# wire_detector.net
KiCad netlist of a schematic drawn in EAGLE
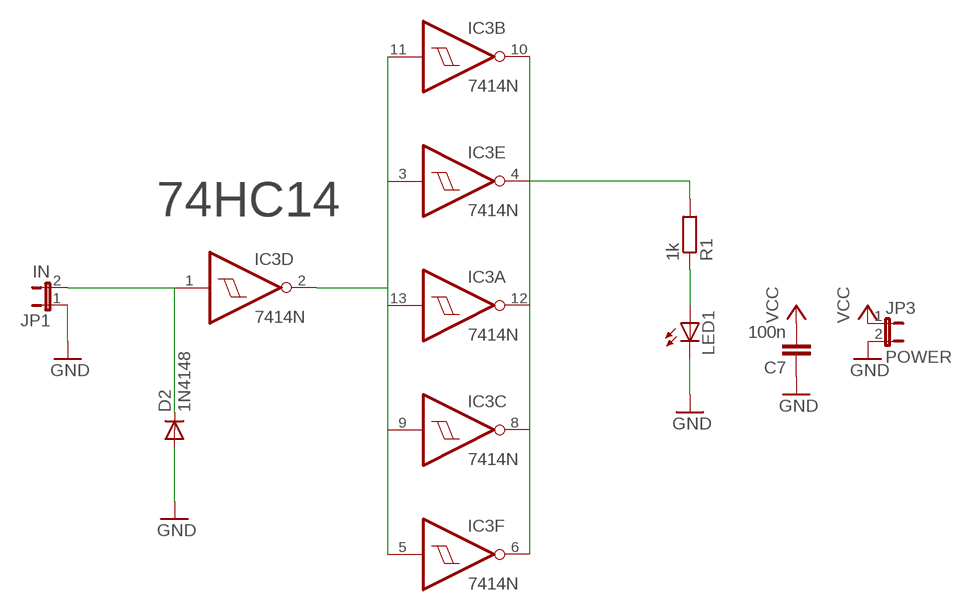
[diagram p0: schematic, sheet 1]

(export (version "E")
  (design (tool "Eeschema 10.0.6"))
  (components
    (comp (ref "C7")
      (value "100n")
      (footprint "eagle-import:C025-024X044")
      (libsource (lib "eagle-import") (part "C-EU025-024X044"))
    )
    (comp (ref "D2")
      (value "1N4148")
      (footprint "eagle-import:D-2.5")
      (libsource (lib "eagle-import") (part "DIODE-D-2.5"))
    )
    (comp (ref "IC3")
      (value "7414N")
      (footprint "eagle-import:DIL14")
      (libsource (lib "eagle-import") (part "7414N"))
    )
    (comp (ref "JP1")
      (value "IN")
      (footprint "eagle-import:JP1")
      (libsource (lib "eagle-import") (part "JP1E"))
    )
    (comp (ref "JP3")
      (value "POWER")
      (footprint "eagle-import:JP1")
      (libsource (lib "eagle-import") (part "JP1E"))
    )
    (comp (ref "LED1")
      (value "LED5MM")
      (footprint "eagle-import:LED5MM")
      (libsource (lib "eagle-import") (part "LED5MM"))
    )
    (comp (ref "R1")
      (value "1k")
      (footprint "eagle-import:0204_5")
      (libsource (lib "eagle-import") (part "R-EU_0204/5"))
    )
  )
  (nets
    (net (code "1") (name "GND") (class "Default")
      (node (ref "C7") (pin "1") (pinfunction "1_1") (pintype "passive"))
      (node (ref "D2") (pin "A") (pinfunction "A_A") (pintype "passive"))
      (node (ref "JP1") (pin "1") (pinfunction "1_1") (pintype "passive"))
      (node (ref "JP3") (pin "2") (pinfunction "2_2") (pintype "passive"))
      (node (ref "LED1") (pin "K") (pinfunction "C_K") (pintype "passive"))
    )
    (net (code "2") (name "Net-(IC3A-I)") (class "Default")
      (node (ref "IC3") (pin "11") (pinfunction "I_11") (pintype "input"))
      (node (ref "IC3") (pin "13") (pinfunction "I_13") (pintype "input"))
      (node (ref "IC3") (pin "2") (pinfunction "O_2") (pintype "output"))
      (node (ref "IC3") (pin "3") (pinfunction "I_3") (pintype "input"))
      (node (ref "IC3") (pin "5") (pinfunction "I_5") (pintype "input"))
      (node (ref "IC3") (pin "9") (pinfunction "I_9") (pintype "input"))
    )
    (net (code "3") (name "Net-(IC3A-O)") (class "Default")
      (node (ref "IC3") (pin "10") (pinfunction "O_10") (pintype "output"))
      (node (ref "IC3") (pin "12") (pinfunction "O_12") (pintype "output"))
      (node (ref "IC3") (pin "4") (pinfunction "O_4") (pintype "output"))
      (node (ref "IC3") (pin "6") (pinfunction "O_6") (pintype "output"))
      (node (ref "IC3") (pin "8") (pinfunction "O_8") (pintype "output"))
      (node (ref "R1") (pin "2") (pinfunction "2_2") (pintype "passive"))
    )
    (net (code "4") (name "Net-(IC3D-I)") (class "Default")
      (node (ref "D2") (pin "C") (pinfunction "C_C") (pintype "passive"))
      (node (ref "IC3") (pin "1") (pinfunction "I_1") (pintype "input"))
      (node (ref "JP1") (pin "2") (pinfunction "2_2") (pintype "passive"))
    )
    (net (code "5") (name "Net-(LED1-PadA)") (class "Default")
      (node (ref "LED1") (pin "A") (pinfunction "A_A") (pintype "passive"))
      (node (ref "R1") (pin "1") (pinfunction "1_1") (pintype "passive"))
    )
    (net (code "6") (name "VCC") (class "Default")
      (node (ref "C7") (pin "2") (pinfunction "2_2") (pintype "passive"))
      (node (ref "JP3") (pin "1") (pinfunction "1_1") (pintype "passive"))
    )
  )
)
